# atkstepper17.net
KiCad netlist of a schematic drawn in EAGLE
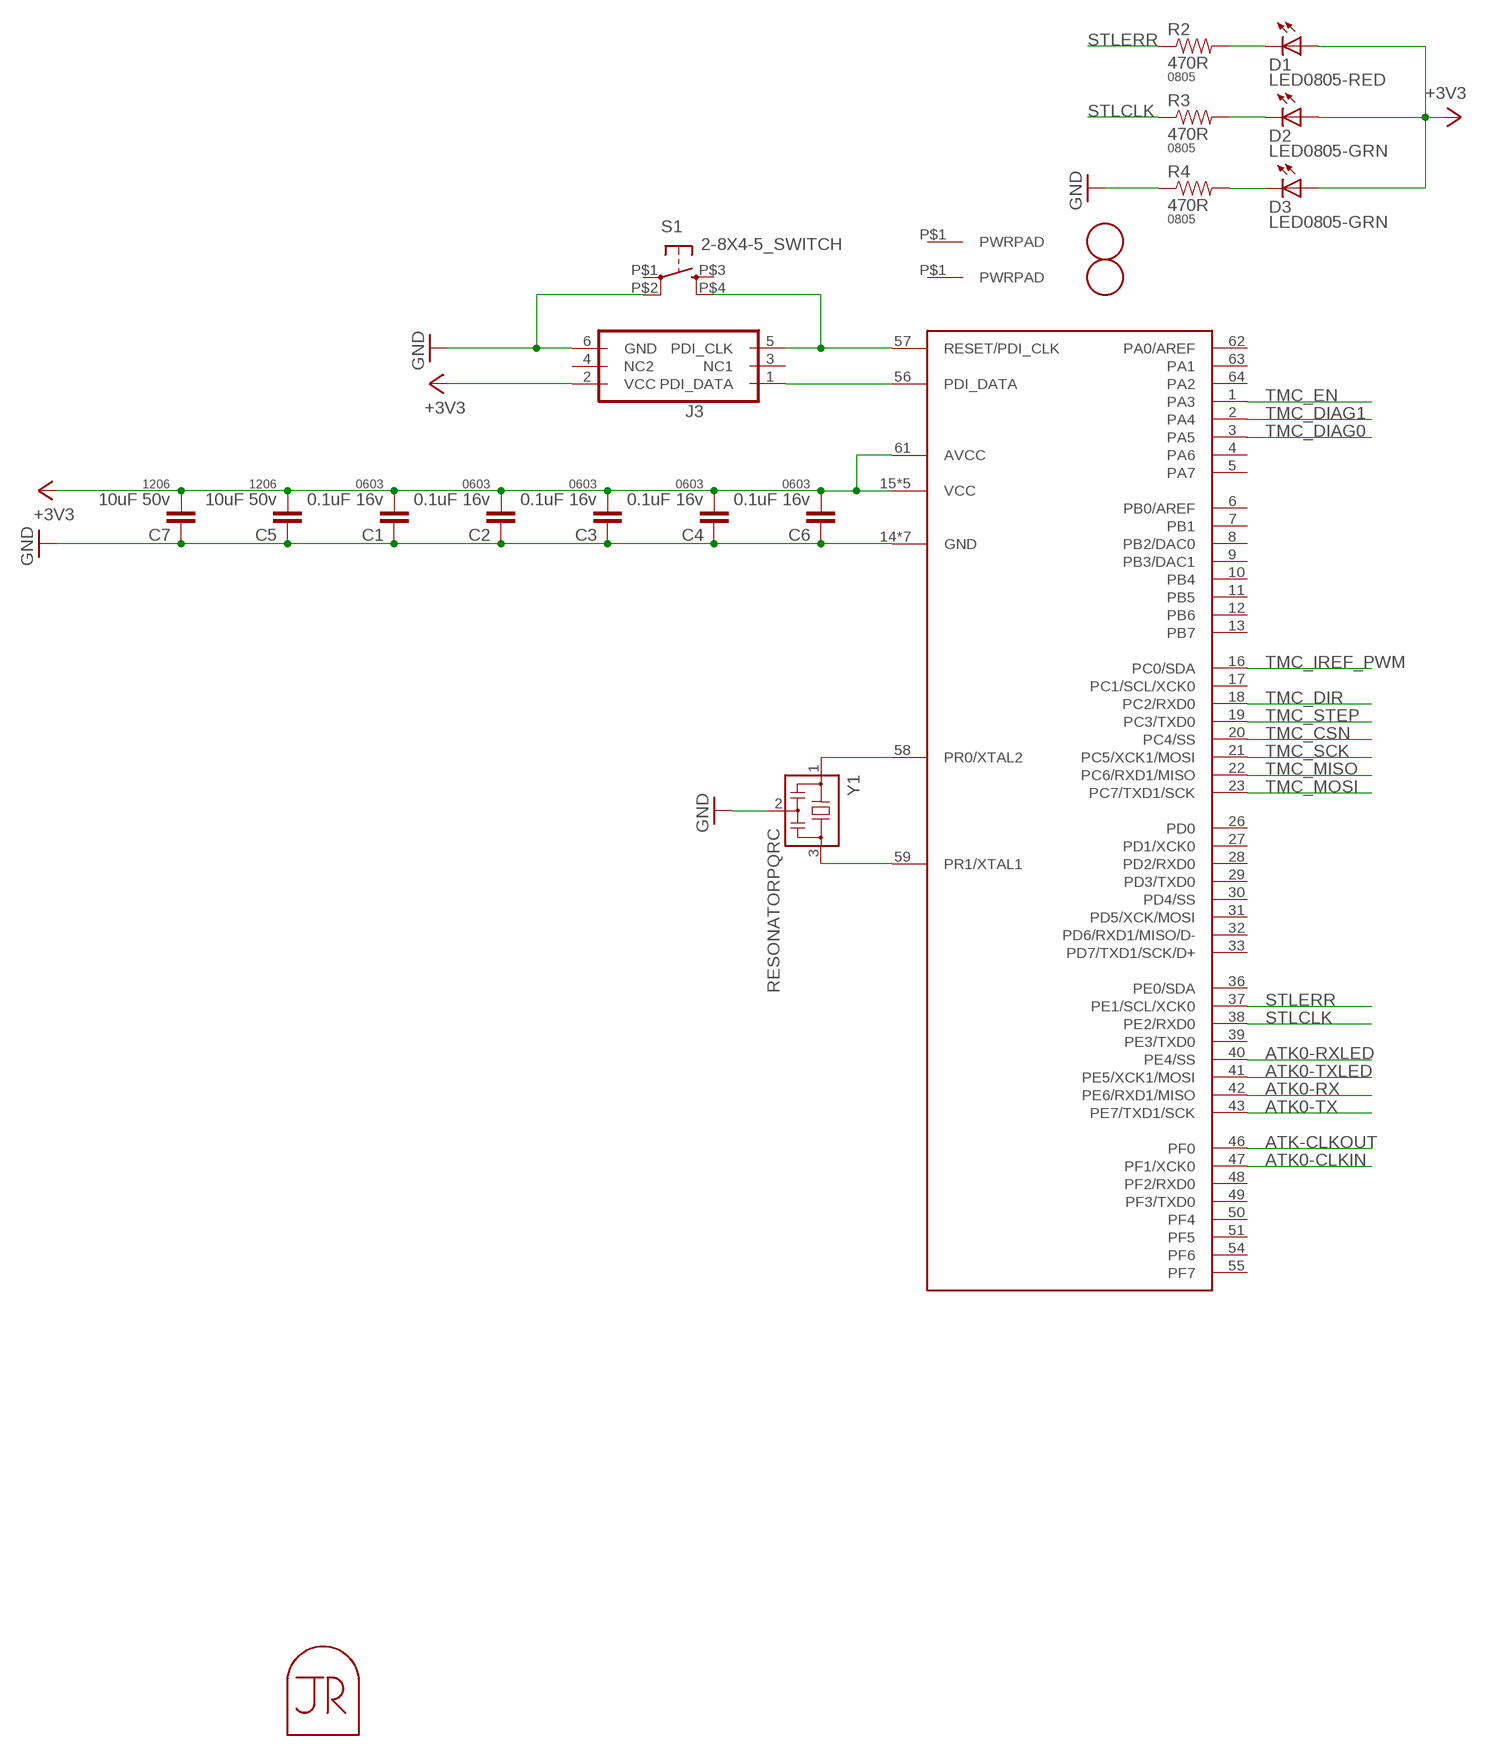
[diagram p0: schematic, sheet 1, part 1 of 2]
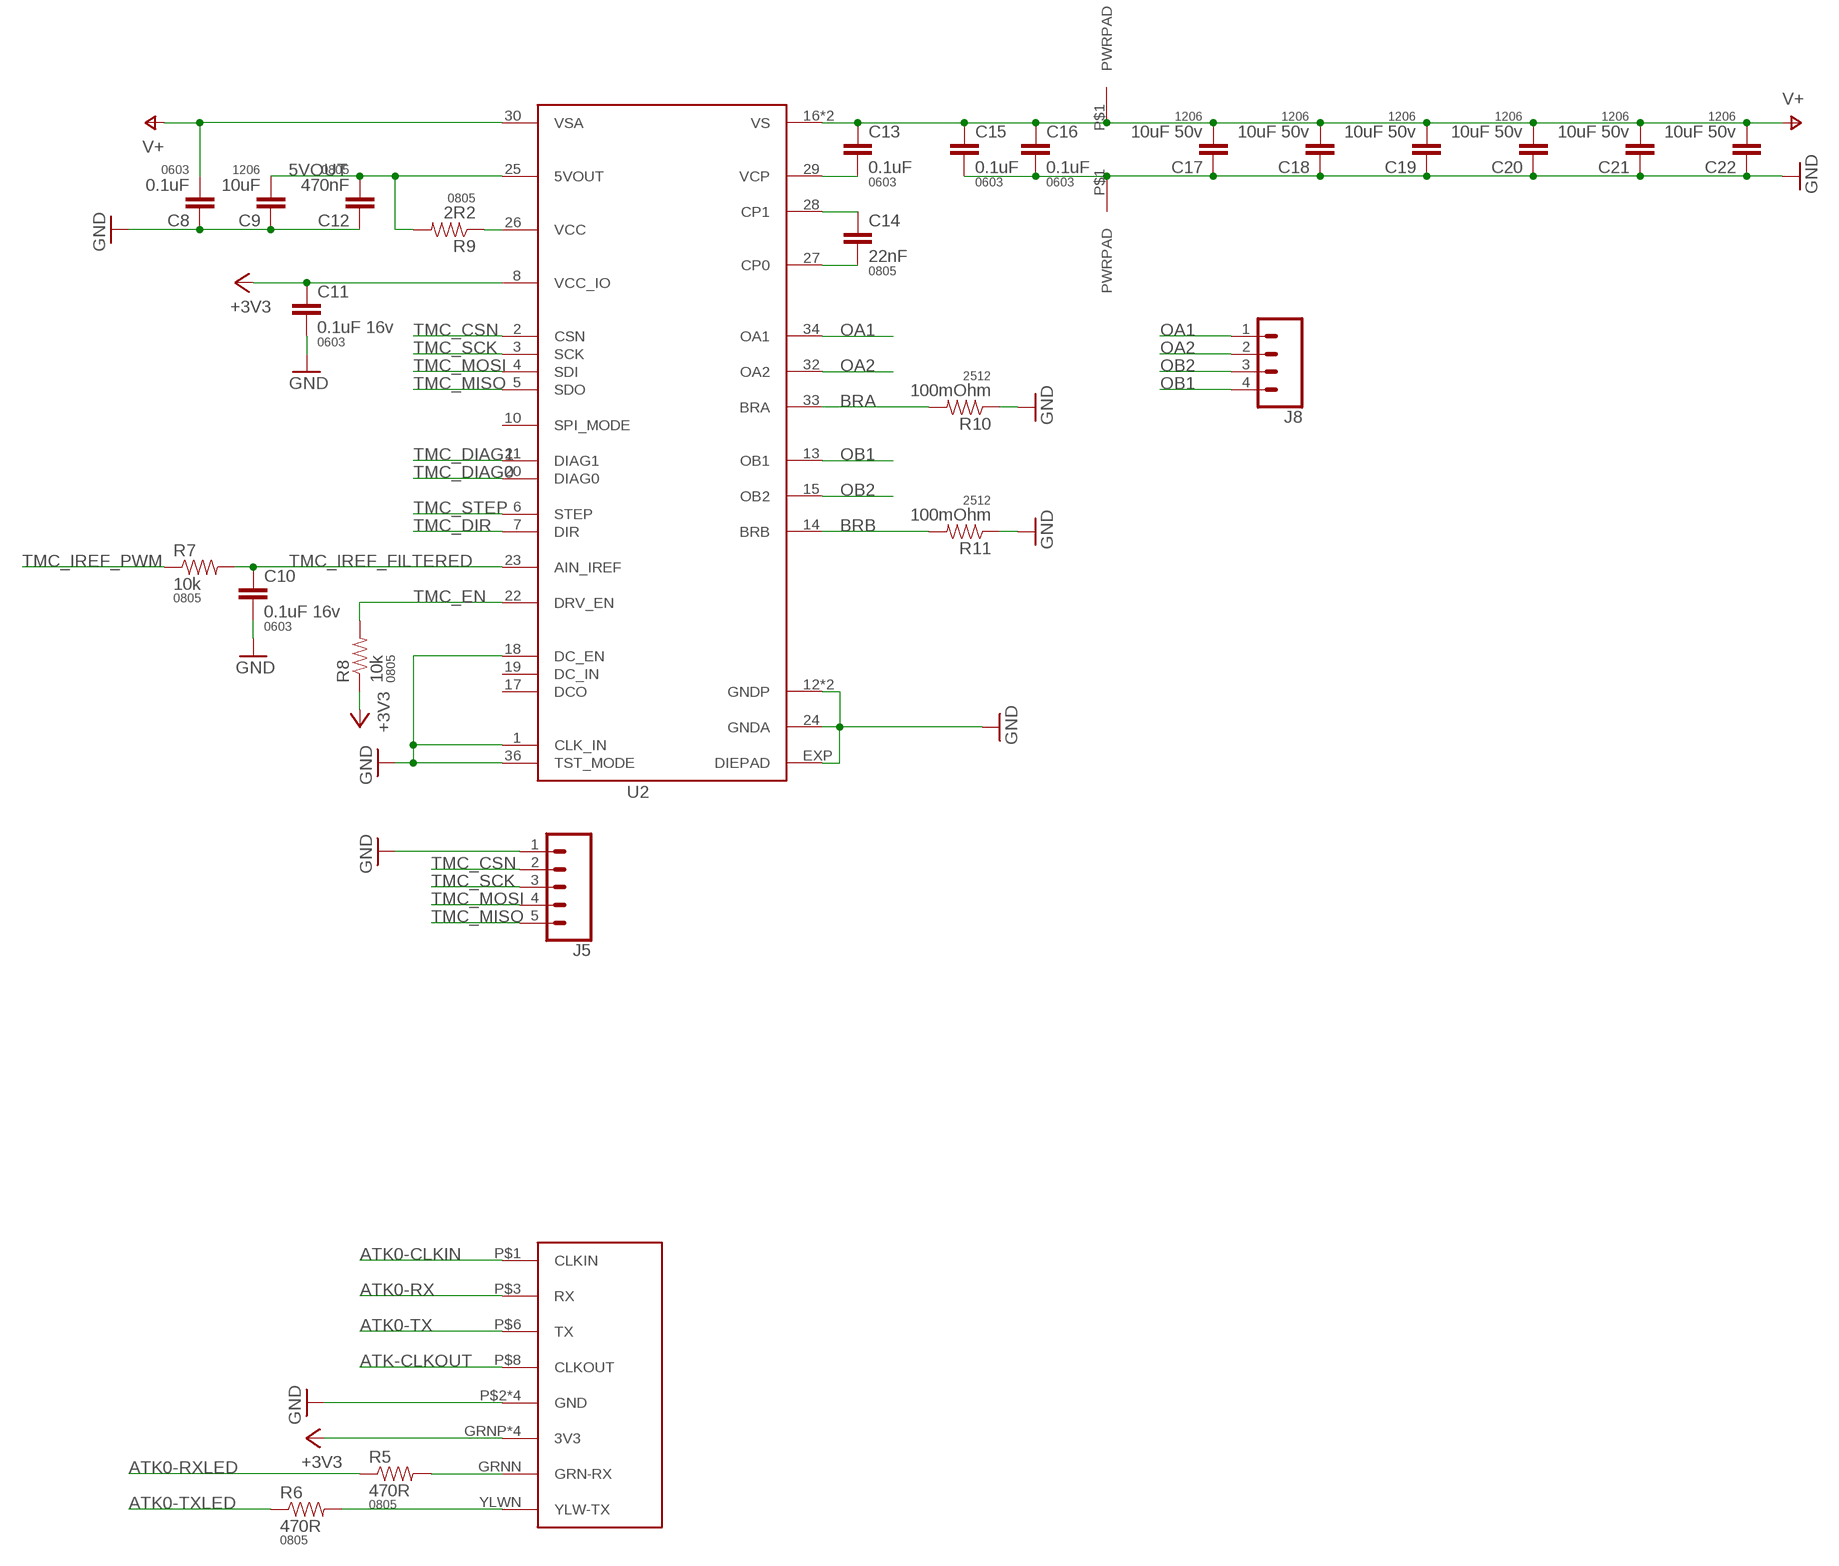
[diagram p1: schematic, sheet 1, part 2 of 2]

(export (version "E")
  (design (tool "Eeschema 10.0.6"))
  (components
    (comp (ref "C1")
      (value "0.1uF 16v")
      (footprint "eagle-import:0603-CAP")
      (libsource (lib "eagle-import") (part "CAP0603-CAP"))
    )
    (comp (ref "C2")
      (value "0.1uF 16v")
      (footprint "eagle-import:0603-CAP")
      (libsource (lib "eagle-import") (part "CAP0603-CAP"))
    )
    (comp (ref "C3")
      (value "0.1uF 16v")
      (footprint "eagle-import:0603-CAP")
      (libsource (lib "eagle-import") (part "CAP0603-CAP"))
    )
    (comp (ref "C4")
      (value "0.1uF 16v")
      (footprint "eagle-import:0603-CAP")
      (libsource (lib "eagle-import") (part "CAP0603-CAP"))
    )
    (comp (ref "C5")
      (value "10uF 50v")
      (footprint "eagle-import:1206")
      (libsource (lib "eagle-import") (part "CAP1206"))
    )
    (comp (ref "C6")
      (value "0.1uF 16v")
      (footprint "eagle-import:0603-CAP")
      (libsource (lib "eagle-import") (part "CAP0603-CAP"))
    )
    (comp (ref "C7")
      (value "10uF 50v")
      (footprint "eagle-import:1206")
      (libsource (lib "eagle-import") (part "CAP1206"))
    )
    (comp (ref "C8")
      (value "0.1uF")
      (footprint "eagle-import:0603-CAP")
      (libsource (lib "eagle-import") (part "CAP0603-CAP"))
    )
    (comp (ref "C9")
      (value "10uF")
      (footprint "eagle-import:1206")
      (libsource (lib "eagle-import") (part "CAP1206"))
    )
    (comp (ref "C10")
      (value "0.1uF 16v")
      (footprint "eagle-import:0603-CAP")
      (libsource (lib "eagle-import") (part "CAP0603-CAP"))
    )
    (comp (ref "C11")
      (value "0.1uF 16v")
      (footprint "eagle-import:0603-CAP")
      (libsource (lib "eagle-import") (part "CAP0603-CAP"))
    )
    (comp (ref "C12")
      (value "470nF")
      (footprint "eagle-import:0805")
      (libsource (lib "eagle-import") (part "CAP0805"))
    )
    (comp (ref "C13")
      (value "0.1uF")
      (footprint "eagle-import:0603-CAP")
      (libsource (lib "eagle-import") (part "CAP0603-CAP"))
    )
    (comp (ref "C14")
      (value "22nF")
      (footprint "eagle-import:0805")
      (libsource (lib "eagle-import") (part "CAP0805"))
    )
    (comp (ref "C15")
      (value "0.1uF")
      (footprint "eagle-import:0603-CAP")
      (libsource (lib "eagle-import") (part "CAP0603-CAP"))
    )
    (comp (ref "C16")
      (value "0.1uF")
      (footprint "eagle-import:0603-CAP")
      (libsource (lib "eagle-import") (part "CAP0603-CAP"))
    )
    (comp (ref "C17")
      (value "10uF 50v")
      (footprint "eagle-import:1206")
      (libsource (lib "eagle-import") (part "CAP1206"))
    )
    (comp (ref "C18")
      (value "10uF 50v")
      (footprint "eagle-import:1206")
      (libsource (lib "eagle-import") (part "CAP1206"))
    )
    (comp (ref "C19")
      (value "10uF 50v")
      (footprint "eagle-import:1206")
      (libsource (lib "eagle-import") (part "CAP1206"))
    )
    (comp (ref "C20")
      (value "10uF 50v")
      (footprint "eagle-import:1206")
      (libsource (lib "eagle-import") (part "CAP1206"))
    )
    (comp (ref "C21")
      (value "10uF 50v")
      (footprint "eagle-import:1206")
      (libsource (lib "eagle-import") (part "CAP1206"))
    )
    (comp (ref "C22")
      (value "10uF 50v")
      (footprint "eagle-import:1206")
      (libsource (lib "eagle-import") (part "CAP1206"))
    )
    (comp (ref "D1")
      (value "LED0805-RED")
      (footprint "eagle-import:LED0805")
      (libsource (lib "eagle-import") (part "LED0805"))
    )
    (comp (ref "D2")
      (value "LED0805-GRN")
      (footprint "eagle-import:LED0805")
      (libsource (lib "eagle-import") (part "LED0805"))
    )
    (comp (ref "D3")
      (value "LED0805-GRN")
      (footprint "eagle-import:LED0805")
      (libsource (lib "eagle-import") (part "LED0805"))
    )
    (comp (ref "J1")
      (value "PWRPADM3")
      (footprint "eagle-import:PWRPAD_3-25MM")
      (libsource (lib "eagle-import") (part "PWRPADM3"))
    )
    (comp (ref "J2")
      (value "PWRPADM3")
      (footprint "eagle-import:PWRPAD_3-25MM")
      (libsource (lib "eagle-import") (part "PWRPADM3"))
    )
    (comp (ref "J3")
      (value "PDIFEMALE_SMD")
      (footprint "eagle-import:PDI_2X3_SMD")
      (libsource (lib "eagle-import") (part "PDIFEMALE_SMD"))
    )
    (comp (ref "J4")
      (value "ATK-PHY")
      (footprint "eagle-import:RJ45-LED-RJE7318800XXX")
      (libsource (lib "eagle-import") (part "ATK-PHY"))
    )
    (comp (ref "J5")
      (value "CONN_05NO_SILK")
      (footprint "eagle-import:1X05_NO_SILK")
      (libsource (lib "eagle-import") (part "CONN_05NO_SILK"))
    )
    (comp (ref "J6")
      (value "PWRPAD")
      (footprint "eagle-import:PWRPAD_M3-PEM-MOUNT")
      (libsource (lib "eagle-import") (part "PWRPAD"))
    )
    (comp (ref "J7")
      (value "PWRPAD")
      (footprint "eagle-import:PWRPAD_M3-PEM-MOUNT")
      (libsource (lib "eagle-import") (part "PWRPAD"))
    )
    (comp (ref "J8")
      (value "CONN_04LONGPADS")
      (footprint "eagle-import:1X04_LONGPADS")
      (libsource (lib "eagle-import") (part "CONN_04LONGPADS"))
    )
    (comp (ref "MP1")
      (value "JRTOMBSTONE")
      (footprint "eagle-import:JRTOMBSTONE")
      (libsource (lib "eagle-import") (part "JRTOMBSTONE"))
    )
    (comp (ref "R2")
      (value "470R")
      (footprint "eagle-import:0805")
      (libsource (lib "eagle-import") (part "RESISTOR0805-RES"))
    )
    (comp (ref "R3")
      (value "470R")
      (footprint "eagle-import:0805")
      (libsource (lib "eagle-import") (part "RESISTOR0805-RES"))
    )
    (comp (ref "R4")
      (value "470R")
      (footprint "eagle-import:0805")
      (libsource (lib "eagle-import") (part "RESISTOR0805-RES"))
    )
    (comp (ref "R5")
      (value "470R")
      (footprint "eagle-import:0805")
      (libsource (lib "eagle-import") (part "RESISTOR0805-RES"))
    )
    (comp (ref "R6")
      (value "470R")
      (footprint "eagle-import:0805")
      (libsource (lib "eagle-import") (part "RESISTOR0805-RES"))
    )
    (comp (ref "R7")
      (value "10k")
      (footprint "eagle-import:0805")
      (libsource (lib "eagle-import") (part "RESISTOR0805-RES"))
    )
    (comp (ref "R8")
      (value "10k")
      (footprint "eagle-import:0805")
      (libsource (lib "eagle-import") (part "RESISTOR0805-RES"))
    )
    (comp (ref "R9")
      (value "2R2")
      (footprint "eagle-import:0805")
      (libsource (lib "eagle-import") (part "RESISTOR0805-RES"))
    )
    (comp (ref "R10")
      (value "100mOhm")
      (footprint "eagle-import:R2512")
      (libsource (lib "eagle-import") (part "RESISTOR2512"))
    )
    (comp (ref "R11")
      (value "100mOhm")
      (footprint "eagle-import:R2512")
      (libsource (lib "eagle-import") (part "RESISTOR2512"))
    )
    (comp (ref "S1")
      (value "2-8X4-5_SWITCH")
      (footprint "eagle-import:TACT-SWITCH-KMR6")
      (libsource (lib "eagle-import") (part "2-8X4-5_SWITCH"))
    )
    (comp (ref "U$1")
      (value "FIDUCIAL")
      (footprint "eagle-import:FIDUCIAL_1MM")
      (libsource (lib "eagle-import") (part "FIDUCIAL"))
    )
    (comp (ref "U$2")
      (value "FIDUCIAL")
      (footprint "eagle-import:FIDUCIAL_1MM")
      (libsource (lib "eagle-import") (part "FIDUCIAL"))
    )
    (comp (ref "U1")
      (value "ATXMEGA_A3UQFN")
      (footprint "eagle-import:QFN-64-9X9MM")
      (libsource (lib "eagle-import") (part "ATXMEGA_A3UQFN"))
    )
    (comp (ref "U2")
      (value "TMC2130")
      (footprint "eagle-import:QFN36-5X6")
      (libsource (lib "eagle-import") (part "TMC2130"))
    )
    (comp (ref "Y1")
      (value "RESONATORPQRC")
      (footprint "eagle-import:RES_PRQC")
      (libsource (lib "eagle-import") (part "RESONATORPQRC"))
    )
  )
  (nets
    (net (code "1") (name "+3V3") (class "Default")
      (node (ref "C1") (pin "2") (pinfunction "2_2") (pintype "passive"))
      (node (ref "C11") (pin "1") (pinfunction "1_1") (pintype "passive"))
      (node (ref "C2") (pin "2") (pinfunction "2_2") (pintype "passive"))
      (node (ref "C3") (pin "2") (pinfunction "2_2") (pintype "passive"))
      (node (ref "C4") (pin "2") (pinfunction "2_2") (pintype "passive"))
      (node (ref "C5") (pin "2") (pinfunction "2_2") (pintype "passive"))
      (node (ref "C6") (pin "2") (pinfunction "2_2") (pintype "passive"))
      (node (ref "C7") (pin "2") (pinfunction "2_2") (pintype "passive"))
      (node (ref "D1") (pin "1") (pinfunction "A_1") (pintype "passive"))
      (node (ref "D2") (pin "1") (pinfunction "A_1") (pintype "passive"))
      (node (ref "D3") (pin "1") (pinfunction "A_1") (pintype "passive"))
      (node (ref "J3") (pin "2") (pinfunction "VCC_2") (pintype "bidirectional"))
      (node (ref "J4") (pin "GRNP") (pinfunction "3V3_GRNP") (pintype "bidirectional"))
      (node (ref "J4") (pin "P$4") (pinfunction "3V3_P$4") (pintype "bidirectional"))
      (node (ref "J4") (pin "P$5") (pinfunction "3V3_P$5") (pintype "bidirectional"))
      (node (ref "J4") (pin "YLWP") (pinfunction "3V3_YLWP") (pintype "bidirectional"))
      (node (ref "R8") (pin "1") (pinfunction "1_1") (pintype "passive"))
      (node (ref "U1") (pin "15") (pinfunction "VCC_15") (pintype "bidirectional"))
      (node (ref "U1") (pin "25") (pinfunction "VCC_25") (pintype "bidirectional"))
      (node (ref "U1") (pin "35") (pinfunction "VCC_35") (pintype "bidirectional"))
      (node (ref "U1") (pin "45") (pinfunction "VCC_45") (pintype "bidirectional"))
      (node (ref "U1") (pin "53") (pinfunction "VCC_53") (pintype "bidirectional"))
      (node (ref "U1") (pin "61") (pinfunction "AVCC_61") (pintype "bidirectional"))
      (node (ref "U2") (pin "8") (pinfunction "VCC_IO_8") (pintype "bidirectional"))
    )
    (net (code "2") (name "/5VOUT") (class "Default")
      (node (ref "C12") (pin "2") (pinfunction "2_2") (pintype "passive"))
      (node (ref "C9") (pin "2") (pinfunction "2_2") (pintype "passive"))
      (node (ref "R9") (pin "2") (pinfunction "2_2") (pintype "passive"))
      (node (ref "U2") (pin "25") (pinfunction "5VOUT_25") (pintype "bidirectional"))
    )
    (net (code "3") (name "/ATK-CLKOUT") (class "Default")
      (node (ref "J4") (pin "P$8") (pinfunction "CLKOUT_P$8") (pintype "bidirectional"))
      (node (ref "U1") (pin "46") (pinfunction "PF0_46") (pintype "bidirectional"))
    )
    (net (code "4") (name "/ATK0-CLKIN") (class "Default")
      (node (ref "J4") (pin "P$1") (pinfunction "CLKIN_P$1") (pintype "bidirectional"))
      (node (ref "U1") (pin "47") (pinfunction "PF1/XCK0_47") (pintype "bidirectional"))
    )
    (net (code "5") (name "/ATK0-RX") (class "Default")
      (node (ref "J4") (pin "P$3") (pinfunction "RX_P$3") (pintype "bidirectional"))
      (node (ref "U1") (pin "42") (pinfunction "PE6/RXD1/MISO_42") (pintype "bidirectional"))
    )
    (net (code "6") (name "/ATK0-RXLED") (class "Default")
      (node (ref "R5") (pin "1") (pinfunction "1_1") (pintype "passive"))
      (node (ref "U1") (pin "40") (pinfunction "PE4/SS_40") (pintype "bidirectional"))
    )
    (net (code "7") (name "/ATK0-TX") (class "Default")
      (node (ref "J4") (pin "P$6") (pinfunction "TX_P$6") (pintype "bidirectional"))
      (node (ref "U1") (pin "43") (pinfunction "PE7/TXD1/SCK_43") (pintype "bidirectional"))
    )
    (net (code "8") (name "/ATK0-TXLED") (class "Default")
      (node (ref "R6") (pin "1") (pinfunction "1_1") (pintype "passive"))
      (node (ref "U1") (pin "41") (pinfunction "PE5/XCK1/MOSI_41") (pintype "bidirectional"))
    )
    (net (code "9") (name "/BRA") (class "Default")
      (node (ref "R10") (pin "2") (pinfunction "2_2") (pintype "passive"))
      (node (ref "U2") (pin "33") (pinfunction "BRA_33") (pintype "bidirectional"))
    )
    (net (code "10") (name "/BRB") (class "Default")
      (node (ref "R11") (pin "2") (pinfunction "2_2") (pintype "passive"))
      (node (ref "U2") (pin "14") (pinfunction "BRB_14") (pintype "bidirectional"))
    )
    (net (code "11") (name "/OA1") (class "Default")
      (node (ref "J8") (pin "1") (pinfunction "1_1") (pintype "passive"))
      (node (ref "U2") (pin "34") (pinfunction "OA1_34") (pintype "bidirectional"))
    )
    (net (code "12") (name "/OA2") (class "Default")
      (node (ref "J8") (pin "2") (pinfunction "2_2") (pintype "passive"))
      (node (ref "U2") (pin "32") (pinfunction "OA2_32") (pintype "bidirectional"))
    )
    (net (code "13") (name "/OB1") (class "Default")
      (node (ref "J8") (pin "4") (pinfunction "4_4") (pintype "passive"))
      (node (ref "U2") (pin "13") (pinfunction "OB1_13") (pintype "bidirectional"))
    )
    (net (code "14") (name "/OB2") (class "Default")
      (node (ref "J8") (pin "3") (pinfunction "3_3") (pintype "passive"))
      (node (ref "U2") (pin "15") (pinfunction "OB2_15") (pintype "bidirectional"))
    )
    (net (code "15") (name "/STLCLK") (class "Default")
      (node (ref "R3") (pin "1") (pinfunction "1_1") (pintype "passive"))
      (node (ref "U1") (pin "38") (pinfunction "PE2/RXD0_38") (pintype "bidirectional"))
    )
    (net (code "16") (name "/STLERR") (class "Default")
      (node (ref "R2") (pin "1") (pinfunction "1_1") (pintype "passive"))
      (node (ref "U1") (pin "37") (pinfunction "PE1/SCL/XCK0_37") (pintype "bidirectional"))
    )
    (net (code "17") (name "/TMC_CSN") (class "Default")
      (node (ref "J5") (pin "2") (pinfunction "2_2") (pintype "passive"))
      (node (ref "U1") (pin "20") (pinfunction "PC4/SS_20") (pintype "bidirectional"))
      (node (ref "U2") (pin "2") (pinfunction "CSN_2") (pintype "bidirectional"))
    )
    (net (code "18") (name "/TMC_DIAG0") (class "Default")
      (node (ref "U1") (pin "3") (pinfunction "PA5_3") (pintype "bidirectional"))
      (node (ref "U2") (pin "20") (pinfunction "DIAG0_20") (pintype "bidirectional"))
    )
    (net (code "19") (name "/TMC_DIAG1") (class "Default")
      (node (ref "U1") (pin "2") (pinfunction "PA4_2") (pintype "bidirectional"))
      (node (ref "U2") (pin "21") (pinfunction "DIAG1_21") (pintype "bidirectional"))
    )
    (net (code "20") (name "/TMC_DIR") (class "Default")
      (node (ref "U1") (pin "18") (pinfunction "PC2/RXD0_18") (pintype "bidirectional"))
      (node (ref "U2") (pin "7") (pinfunction "DIR_7") (pintype "bidirectional"))
    )
    (net (code "21") (name "/TMC_EN") (class "Default")
      (node (ref "R8") (pin "2") (pinfunction "2_2") (pintype "passive"))
      (node (ref "U1") (pin "1") (pinfunction "PA3_1") (pintype "bidirectional"))
      (node (ref "U2") (pin "22") (pinfunction "DRV_EN_22") (pintype "bidirectional"))
    )
    (net (code "22") (name "/TMC_IREF_FILTERED") (class "Default")
      (node (ref "C10") (pin "1") (pinfunction "1_1") (pintype "passive"))
      (node (ref "R7") (pin "2") (pinfunction "2_2") (pintype "passive"))
      (node (ref "U2") (pin "23") (pinfunction "AIN_IREF_23") (pintype "bidirectional"))
    )
    (net (code "23") (name "/TMC_IREF_PWM") (class "Default")
      (node (ref "R7") (pin "1") (pinfunction "1_1") (pintype "passive"))
      (node (ref "U1") (pin "16") (pinfunction "PC0/SDA_16") (pintype "bidirectional"))
    )
    (net (code "24") (name "/TMC_MISO") (class "Default")
      (node (ref "J5") (pin "5") (pinfunction "5_5") (pintype "passive"))
      (node (ref "U1") (pin "22") (pinfunction "PC6/RXD1/MISO_22") (pintype "bidirectional"))
      (node (ref "U2") (pin "5") (pinfunction "SDO_5") (pintype "bidirectional"))
    )
    (net (code "25") (name "/TMC_MOSI") (class "Default")
      (node (ref "J5") (pin "4") (pinfunction "4_4") (pintype "passive"))
      (node (ref "U1") (pin "23") (pinfunction "PC7/TXD1/SCK_23") (pintype "bidirectional"))
      (node (ref "U2") (pin "4") (pinfunction "SDI_4") (pintype "bidirectional"))
    )
    (net (code "26") (name "/TMC_SCK") (class "Default")
      (node (ref "J5") (pin "3") (pinfunction "3_3") (pintype "passive"))
      (node (ref "U1") (pin "21") (pinfunction "PC5/XCK1/MOSI_21") (pintype "bidirectional"))
      (node (ref "U2") (pin "3") (pinfunction "SCK_3") (pintype "bidirectional"))
    )
    (net (code "27") (name "/TMC_STEP") (class "Default")
      (node (ref "U1") (pin "19") (pinfunction "PC3/TXD0_19") (pintype "bidirectional"))
      (node (ref "U2") (pin "6") (pinfunction "STEP_6") (pintype "bidirectional"))
    )
    (net (code "28") (name "GND") (class "Default")
      (node (ref "C1") (pin "1") (pinfunction "1_1") (pintype "passive"))
      (node (ref "C10") (pin "2") (pinfunction "2_2") (pintype "passive"))
      (node (ref "C11") (pin "2") (pinfunction "2_2") (pintype "passive"))
      (node (ref "C12") (pin "1") (pinfunction "1_1") (pintype "passive"))
      (node (ref "C15") (pin "2") (pinfunction "2_2") (pintype "passive"))
      (node (ref "C16") (pin "2") (pinfunction "2_2") (pintype "passive"))
      (node (ref "C17") (pin "1") (pinfunction "1_1") (pintype "passive"))
      (node (ref "C18") (pin "1") (pinfunction "1_1") (pintype "passive"))
      (node (ref "C19") (pin "1") (pinfunction "1_1") (pintype "passive"))
      (node (ref "C2") (pin "1") (pinfunction "1_1") (pintype "passive"))
      (node (ref "C20") (pin "1") (pinfunction "1_1") (pintype "passive"))
      (node (ref "C21") (pin "1") (pinfunction "1_1") (pintype "passive"))
      (node (ref "C22") (pin "1") (pinfunction "1_1") (pintype "passive"))
      (node (ref "C3") (pin "1") (pinfunction "1_1") (pintype "passive"))
      (node (ref "C4") (pin "1") (pinfunction "1_1") (pintype "passive"))
      (node (ref "C5") (pin "1") (pinfunction "1_1") (pintype "passive"))
      (node (ref "C6") (pin "1") (pinfunction "1_1") (pintype "passive"))
      (node (ref "C7") (pin "1") (pinfunction "1_1") (pintype "passive"))
      (node (ref "C8") (pin "1") (pinfunction "1_1") (pintype "passive"))
      (node (ref "C9") (pin "1") (pinfunction "1_1") (pintype "passive"))
      (node (ref "J3") (pin "6") (pinfunction "GND_6") (pintype "bidirectional"))
      (node (ref "J4") (pin "P$2") (pinfunction "GND_P$2") (pintype "bidirectional"))
      (node (ref "J4") (pin "P$7") (pinfunction "GND_P$7") (pintype "bidirectional"))
      (node (ref "J4") (pin "SHDL1") (pinfunction "GND_SHDL1") (pintype "bidirectional"))
      (node (ref "J4") (pin "SHDL2") (pinfunction "GND_SHDL2") (pintype "bidirectional"))
      (node (ref "J5") (pin "1") (pinfunction "1_1") (pintype "passive"))
      (node (ref "J7") (pin "P$1") (pinfunction "PWRPAD_P$1") (pintype "bidirectional"))
      (node (ref "R10") (pin "1") (pinfunction "1_1") (pintype "passive"))
      (node (ref "R11") (pin "1") (pinfunction "1_1") (pintype "passive"))
      (node (ref "R4") (pin "1") (pinfunction "1_1") (pintype "passive"))
      (node (ref "S1") (pin "P$2") (pinfunction "P1_P$2") (pintype "passive"))
      (node (ref "U1") (pin "14") (pinfunction "GND_14") (pintype "bidirectional"))
      (node (ref "U1") (pin "24") (pinfunction "GND_24") (pintype "bidirectional"))
      (node (ref "U1") (pin "34") (pinfunction "GND_34") (pintype "bidirectional"))
      (node (ref "U1") (pin "44") (pinfunction "GND_44") (pintype "bidirectional"))
      (node (ref "U1") (pin "52") (pinfunction "GND_52") (pintype "bidirectional"))
      (node (ref "U1") (pin "60") (pinfunction "GND_60") (pintype "bidirectional"))
      (node (ref "U1") (pin "P$1") (pinfunction "GND_P$1") (pintype "bidirectional"))
      (node (ref "U2") (pin "1") (pinfunction "CLK_IN_1") (pintype "bidirectional"))
      (node (ref "U2") (pin "12") (pinfunction "GNDP_12") (pintype "bidirectional"))
      (node (ref "U2") (pin "18") (pinfunction "DC_EN_18") (pintype "bidirectional"))
      (node (ref "U2") (pin "24") (pinfunction "GNDA_24") (pintype "bidirectional"))
      (node (ref "U2") (pin "35") (pinfunction "GNDP_35") (pintype "bidirectional"))
      (node (ref "U2") (pin "36") (pinfunction "TST_MODE_36") (pintype "bidirectional"))
      (node (ref "U2") (pin "EXP") (pinfunction "DIEPAD_EXP") (pintype "bidirectional"))
      (node (ref "Y1") (pin "2") (pinfunction "2_2") (pintype "passive"))
    )
    (net (code "29") (name "Net-(D1-C)") (class "Default")
      (node (ref "D1") (pin "2") (pinfunction "C_2") (pintype "passive"))
      (node (ref "R2") (pin "2") (pinfunction "2_2") (pintype "passive"))
    )
    (net (code "30") (name "Net-(D2-C)") (class "Default")
      (node (ref "D2") (pin "2") (pinfunction "C_2") (pintype "passive"))
      (node (ref "R3") (pin "2") (pinfunction "2_2") (pintype "passive"))
    )
    (net (code "31") (name "Net-(D3-C)") (class "Default")
      (node (ref "D3") (pin "2") (pinfunction "C_2") (pintype "passive"))
      (node (ref "R4") (pin "2") (pinfunction "2_2") (pintype "passive"))
    )
    (net (code "32") (name "Net-(J3-PDI_CLK)") (class "Default")
      (node (ref "J3") (pin "5") (pinfunction "PDI_CLK_5") (pintype "bidirectional"))
      (node (ref "S1") (pin "P$4") (pinfunction "S1_P$4") (pintype "passive"))
      (node (ref "U1") (pin "57") (pinfunction "RESET/PDI_CLK_57") (pintype "bidirectional"))
    )
    (net (code "33") (name "Net-(J3-PDI_DATA)") (class "Default")
      (node (ref "J3") (pin "1") (pinfunction "PDI_DATA_1") (pintype "bidirectional"))
      (node (ref "U1") (pin "56") (pinfunction "PDI_DATA_56") (pintype "bidirectional"))
    )
    (net (code "34") (name "Net-(J4-GRN-RX)") (class "Default")
      (node (ref "J4") (pin "GRNN") (pinfunction "GRN-RX_GRNN") (pintype "bidirectional"))
      (node (ref "R5") (pin "2") (pinfunction "2_2") (pintype "passive"))
    )
    (net (code "35") (name "Net-(J4-YLW-TX)") (class "Default")
      (node (ref "J4") (pin "YLWN") (pinfunction "YLW-TX_YLWN") (pintype "bidirectional"))
      (node (ref "R6") (pin "2") (pinfunction "2_2") (pintype "passive"))
    )
    (net (code "36") (name "Net-(U1-PR0{slash}XTAL2)") (class "Default")
      (node (ref "U1") (pin "58") (pinfunction "PR0/XTAL2_58") (pintype "bidirectional"))
      (node (ref "Y1") (pin "1") (pinfunction "1_1") (pintype "passive"))
    )
    (net (code "37") (name "Net-(U1-PR1{slash}XTAL1)") (class "Default")
      (node (ref "U1") (pin "59") (pinfunction "PR1/XTAL1_59") (pintype "bidirectional"))
      (node (ref "Y1") (pin "3") (pinfunction "3_3") (pintype "passive"))
    )
    (net (code "38") (name "Net-(U2-CP0)") (class "Default")
      (node (ref "C14") (pin "2") (pinfunction "2_2") (pintype "passive"))
      (node (ref "U2") (pin "27") (pinfunction "CP0_27") (pintype "bidirectional"))
    )
    (net (code "39") (name "Net-(U2-CP1)") (class "Default")
      (node (ref "C14") (pin "1") (pinfunction "1_1") (pintype "passive"))
      (node (ref "U2") (pin "28") (pinfunction "CP1_28") (pintype "bidirectional"))
    )
    (net (code "40") (name "Net-(U2-VCC)") (class "Default")
      (node (ref "R9") (pin "1") (pinfunction "1_1") (pintype "passive"))
      (node (ref "U2") (pin "26") (pinfunction "VCC_26") (pintype "bidirectional"))
    )
    (net (code "41") (name "Net-(U2-VCP)") (class "Default")
      (node (ref "C13") (pin "2") (pinfunction "2_2") (pintype "passive"))
      (node (ref "U2") (pin "29") (pinfunction "VCP_29") (pintype "bidirectional"))
    )
    (net (code "42") (name "V+") (class "Default")
      (node (ref "C13") (pin "1") (pinfunction "1_1") (pintype "passive"))
      (node (ref "C15") (pin "1") (pinfunction "1_1") (pintype "passive"))
      (node (ref "C16") (pin "1") (pinfunction "1_1") (pintype "passive"))
      (node (ref "C17") (pin "2") (pinfunction "2_2") (pintype "passive"))
      (node (ref "C18") (pin "2") (pinfunction "2_2") (pintype "passive"))
      (node (ref "C19") (pin "2") (pinfunction "2_2") (pintype "passive"))
      (node (ref "C20") (pin "2") (pinfunction "2_2") (pintype "passive"))
      (node (ref "C21") (pin "2") (pinfunction "2_2") (pintype "passive"))
      (node (ref "C22") (pin "2") (pinfunction "2_2") (pintype "passive"))
      (node (ref "C8") (pin "2") (pinfunction "2_2") (pintype "passive"))
      (node (ref "J6") (pin "P$1") (pinfunction "PWRPAD_P$1") (pintype "bidirectional"))
      (node (ref "U2") (pin "16") (pinfunction "VS_16") (pintype "bidirectional"))
      (node (ref "U2") (pin "30") (pinfunction "VSA_30") (pintype "bidirectional"))
      (node (ref "U2") (pin "31") (pinfunction "VS_31") (pintype "bidirectional"))
    )
    (net (code "43") (name "unconnected-(J1-PWRPAD-PadP$1)") (class "Default")
      (node (ref "J1") (pin "P$1") (pinfunction "PWRPAD_P$1") (pintype "bidirectional"))
    )
    (net (code "44") (name "unconnected-(J2-PWRPAD-PadP$1)") (class "Default")
      (node (ref "J2") (pin "P$1") (pinfunction "PWRPAD_P$1") (pintype "bidirectional"))
    )
    (net (code "45") (name "unconnected-(J3-NC1-Pad3)") (class "Default")
      (node (ref "J3") (pin "3") (pinfunction "NC1_3") (pintype "bidirectional"))
    )
    (net (code "46") (name "unconnected-(J3-NC2-Pad4)") (class "Default")
      (node (ref "J3") (pin "4") (pinfunction "NC2_4") (pintype "bidirectional"))
    )
    (net (code "47") (name "unconnected-(S1-P-PadP$1)") (class "Default")
      (node (ref "S1") (pin "P$1") (pinfunction "P_P$1") (pintype "passive"))
    )
    (net (code "48") (name "unconnected-(S1-S-PadP$3)") (class "Default")
      (node (ref "S1") (pin "P$3") (pinfunction "S_P$3") (pintype "passive"))
    )
    (net (code "49") (name "unconnected-(U1-PA0{slash}AREF-Pad62)") (class "Default")
      (node (ref "U1") (pin "62") (pinfunction "PA0/AREF_62") (pintype "bidirectional"))
    )
    (net (code "50") (name "unconnected-(U1-PA1-Pad63)") (class "Default")
      (node (ref "U1") (pin "63") (pinfunction "PA1_63") (pintype "bidirectional"))
    )
    (net (code "51") (name "unconnected-(U1-PA2-Pad64)") (class "Default")
      (node (ref "U1") (pin "64") (pinfunction "PA2_64") (pintype "bidirectional"))
    )
    (net (code "52") (name "unconnected-(U1-PA6-Pad4)") (class "Default")
      (node (ref "U1") (pin "4") (pinfunction "PA6_4") (pintype "bidirectional"))
    )
    (net (code "53") (name "unconnected-(U1-PA7-Pad5)") (class "Default")
      (node (ref "U1") (pin "5") (pinfunction "PA7_5") (pintype "bidirectional"))
    )
    (net (code "54") (name "unconnected-(U1-PB0{slash}AREF-Pad6)") (class "Default")
      (node (ref "U1") (pin "6") (pinfunction "PB0/AREF_6") (pintype "bidirectional"))
    )
    (net (code "55") (name "unconnected-(U1-PB1-Pad7)") (class "Default")
      (node (ref "U1") (pin "7") (pinfunction "PB1_7") (pintype "bidirectional"))
    )
    (net (code "56") (name "unconnected-(U1-PB2{slash}DAC0-Pad8)") (class "Default")
      (node (ref "U1") (pin "8") (pinfunction "PB2/DAC0_8") (pintype "bidirectional"))
    )
    (net (code "57") (name "unconnected-(U1-PB3{slash}DAC1-Pad9)") (class "Default")
      (node (ref "U1") (pin "9") (pinfunction "PB3/DAC1_9") (pintype "bidirectional"))
    )
    (net (code "58") (name "unconnected-(U1-PB4-Pad10)") (class "Default")
      (node (ref "U1") (pin "10") (pinfunction "PB4_10") (pintype "bidirectional"))
    )
    (net (code "59") (name "unconnected-(U1-PB5-Pad11)") (class "Default")
      (node (ref "U1") (pin "11") (pinfunction "PB5_11") (pintype "bidirectional"))
    )
    (net (code "60") (name "unconnected-(U1-PB6-Pad12)") (class "Default")
      (node (ref "U1") (pin "12") (pinfunction "PB6_12") (pintype "bidirectional"))
    )
    (net (code "61") (name "unconnected-(U1-PB7-Pad13)") (class "Default")
      (node (ref "U1") (pin "13") (pinfunction "PB7_13") (pintype "bidirectional"))
    )
    (net (code "62") (name "unconnected-(U1-PC1{slash}SCL{slash}XCK0-Pad17)") (class "Default")
      (node (ref "U1") (pin "17") (pinfunction "PC1/SCL/XCK0_17") (pintype "bidirectional"))
    )
    (net (code "63") (name "unconnected-(U1-PD0-Pad26)") (class "Default")
      (node (ref "U1") (pin "26") (pinfunction "PD0_26") (pintype "bidirectional"))
    )
    (net (code "64") (name "unconnected-(U1-PD1{slash}XCK0-Pad27)") (class "Default")
      (node (ref "U1") (pin "27") (pinfunction "PD1/XCK0_27") (pintype "bidirectional"))
    )
    (net (code "65") (name "unconnected-(U1-PD2{slash}RXD0-Pad28)") (class "Default")
      (node (ref "U1") (pin "28") (pinfunction "PD2/RXD0_28") (pintype "bidirectional"))
    )
    (net (code "66") (name "unconnected-(U1-PD3{slash}TXD0-Pad29)") (class "Default")
      (node (ref "U1") (pin "29") (pinfunction "PD3/TXD0_29") (pintype "bidirectional"))
    )
    (net (code "67") (name "unconnected-(U1-PD4{slash}SS-Pad30)") (class "Default")
      (node (ref "U1") (pin "30") (pinfunction "PD4/SS_30") (pintype "bidirectional"))
    )
    (net (code "68") (name "unconnected-(U1-PD5{slash}XCK{slash}MOSI-Pad31)") (class "Default")
      (node (ref "U1") (pin "31") (pinfunction "PD5/XCK/MOSI_31") (pintype "bidirectional"))
    )
    (net (code "69") (name "unconnected-(U1-PD6{slash}RXD1{slash}MISO{slash}D--Pad32)") (class "Default")
      (node (ref "U1") (pin "32") (pinfunction "PD6/RXD1/MISO/D-_32") (pintype "bidirectional"))
    )
    (net (code "70") (name "unconnected-(U1-PD7{slash}TXD1{slash}SCK{slash}D+-Pad33)") (class "Default")
      (node (ref "U1") (pin "33") (pinfunction "PD7/TXD1/SCK/D+_33") (pintype "bidirectional"))
    )
    (net (code "71") (name "unconnected-(U1-PE0{slash}SDA-Pad36)") (class "Default")
      (node (ref "U1") (pin "36") (pinfunction "PE0/SDA_36") (pintype "bidirectional"))
    )
    (net (code "72") (name "unconnected-(U1-PE3{slash}TXD0-Pad39)") (class "Default")
      (node (ref "U1") (pin "39") (pinfunction "PE3/TXD0_39") (pintype "bidirectional"))
    )
    (net (code "73") (name "unconnected-(U1-PF2{slash}RXD0-Pad48)") (class "Default")
      (node (ref "U1") (pin "48") (pinfunction "PF2/RXD0_48") (pintype "bidirectional"))
    )
    (net (code "74") (name "unconnected-(U1-PF3{slash}TXD0-Pad49)") (class "Default")
      (node (ref "U1") (pin "49") (pinfunction "PF3/TXD0_49") (pintype "bidirectional"))
    )
    (net (code "75") (name "unconnected-(U1-PF4-Pad50)") (class "Default")
      (node (ref "U1") (pin "50") (pinfunction "PF4_50") (pintype "bidirectional"))
    )
    (net (code "76") (name "unconnected-(U1-PF5-Pad51)") (class "Default")
      (node (ref "U1") (pin "51") (pinfunction "PF5_51") (pintype "bidirectional"))
    )
    (net (code "77") (name "unconnected-(U1-PF6-Pad54)") (class "Default")
      (node (ref "U1") (pin "54") (pinfunction "PF6_54") (pintype "bidirectional"))
    )
    (net (code "78") (name "unconnected-(U1-PF7-Pad55)") (class "Default")
      (node (ref "U1") (pin "55") (pinfunction "PF7_55") (pintype "bidirectional"))
    )
    (net (code "79") (name "unconnected-(U2-DCO-Pad17)") (class "Default")
      (node (ref "U2") (pin "17") (pinfunction "DCO_17") (pintype "bidirectional"))
    )
    (net (code "80") (name "unconnected-(U2-DC_IN-Pad19)") (class "Default")
      (node (ref "U2") (pin "19") (pinfunction "DC_IN_19") (pintype "bidirectional"))
    )
    (net (code "81") (name "unconnected-(U2-SPI_MODE-Pad10)") (class "Default")
      (node (ref "U2") (pin "10") (pinfunction "SPI_MODE_10") (pintype "bidirectional"))
    )
  )
)
